# Leds_Indicadores.net
KiCad netlist of a schematic drawn in Altium Designer
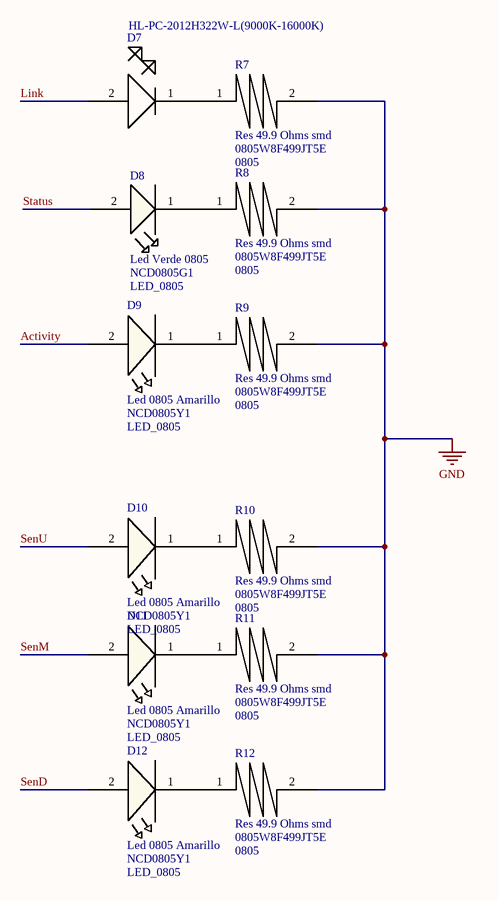
[diagram p0: Leds Indicadores.SchDoc]

(export (version "E")
  (design (tool "Eeschema 10.0.6"))
  (components
    (comp (ref "D7")
      (value "HL-PC-2012H322W-L(9000K-16000K)")
      (footprint "Led 0805 White")
      (libsource (lib "Integrated_Library") (part "LED White 0805"))
    )
    (comp (ref "D8")
      (value "Led Verde 0805")
      (footprint "Led 0805 Verde")
      (fields (field (name "MFR.PART #") "NCD0805G1") (field (name "PACKAGE") "LED_0805"))
      (libsource (lib "Integrated_Library") (part "Led 0805 Verde"))
    )
    (comp (ref "D9")
      (value "Led 0805 Amarillo")
      (footprint "Led 0805 Amarillo")
      (description "NCD0805Y1")
      (fields (field (name "MFR.PART #") "NCD0805Y1") (field (name "PACKAGE") "LED_0805"))
      (libsource (lib "Integrated_Library") (part "Led 0805 Amarillo"))
    )
    (comp (ref "D10")
      (value "Led 0805 Amarillo")
      (footprint "Led 0805 Amarillo")
      (description "NCD0805Y1")
      (fields (field (name "MFR.PART #") "NCD0805Y1") (field (name "PACKAGE") "LED_0805"))
      (libsource (lib "Integrated_Library") (part "Led 0805 Amarillo"))
    )
    (comp (ref "D11")
      (value "Led 0805 Amarillo")
      (footprint "Led 0805 Amarillo")
      (description "NCD0805Y1")
      (fields (field (name "MFR.PART #") "NCD0805Y1") (field (name "PACKAGE") "LED_0805"))
      (libsource (lib "Integrated_Library") (part "Led 0805 Amarillo"))
    )
    (comp (ref "D12")
      (value "Led 0805 Amarillo")
      (footprint "Led 0805 Amarillo")
      (description "NCD0805Y1")
      (fields (field (name "MFR.PART #") "NCD0805Y1") (field (name "PACKAGE") "LED_0805"))
      (libsource (lib "Integrated_Library") (part "Led 0805 Amarillo"))
    )
    (comp (ref "R7")
      (value "Res 49.9 Ohms smd")
      (footprint "RES 49.9 OHMS")
      (fields (field (name "MFR.PART #") "0805W8F499JT5E") (field (name "PACKAGE") "0805"))
      (libsource (lib "Integrated_Library") (part "Res 49.9 Ohms smd"))
    )
    (comp (ref "R8")
      (value "Res 49.9 Ohms smd")
      (footprint "RES 49.9 OHMS")
      (fields (field (name "MFR.PART #") "0805W8F499JT5E") (field (name "PACKAGE") "0805"))
      (libsource (lib "Integrated_Library") (part "Res 49.9 Ohms smd"))
    )
    (comp (ref "R9")
      (value "Res 49.9 Ohms smd")
      (footprint "RES 49.9 OHMS")
      (fields (field (name "MFR.PART #") "0805W8F499JT5E") (field (name "PACKAGE") "0805"))
      (libsource (lib "Integrated_Library") (part "Res 49.9 Ohms smd"))
    )
    (comp (ref "R10")
      (value "Res 49.9 Ohms smd")
      (footprint "RES 49.9 OHMS")
      (fields (field (name "MFR.PART #") "0805W8F499JT5E") (field (name "PACKAGE") "0805"))
      (libsource (lib "Integrated_Library") (part "Res 49.9 Ohms smd"))
    )
    (comp (ref "R11")
      (value "Res 49.9 Ohms smd")
      (footprint "RES 49.9 OHMS")
      (fields (field (name "MFR.PART #") "0805W8F499JT5E") (field (name "PACKAGE") "0805"))
      (libsource (lib "Integrated_Library") (part "Res 49.9 Ohms smd"))
    )
    (comp (ref "R12")
      (value "Res 49.9 Ohms smd")
      (footprint "RES 49.9 OHMS")
      (fields (field (name "MFR.PART #") "0805W8F499JT5E") (field (name "PACKAGE") "0805"))
      (libsource (lib "Integrated_Library") (part "Res 49.9 Ohms smd"))
    )
  )
  (nets
    (net (code "1") (name "/Activity") (class "Default")
      (node (ref "D9") (pin "2") (pinfunction "2_2") (pintype "passive"))
    )
    (net (code "2") (name "/Link") (class "Default")
      (node (ref "D7") (pin "2") (pinfunction "2_2") (pintype "passive"))
    )
    (net (code "3") (name "/SenD") (class "Default")
      (node (ref "D12") (pin "2") (pinfunction "2_2") (pintype "passive"))
    )
    (net (code "4") (name "/SenM") (class "Default")
      (node (ref "D11") (pin "2") (pinfunction "2_2") (pintype "passive"))
    )
    (net (code "5") (name "/SenU") (class "Default")
      (node (ref "D10") (pin "2") (pinfunction "2_2") (pintype "passive"))
    )
    (net (code "6") (name "/Status") (class "Default")
      (node (ref "D8") (pin "2") (pinfunction "2_2") (pintype "passive"))
    )
    (net (code "7") (name "GND") (class "Default")
      (node (ref "R10") (pin "2") (pinfunction "2_2") (pintype "passive"))
      (node (ref "R11") (pin "2") (pinfunction "2_2") (pintype "passive"))
      (node (ref "R12") (pin "2") (pinfunction "2_2") (pintype "passive"))
      (node (ref "R7") (pin "2") (pinfunction "2_2") (pintype "passive"))
      (node (ref "R8") (pin "2") (pinfunction "2_2") (pintype "passive"))
      (node (ref "R9") (pin "2") (pinfunction "2_2") (pintype "passive"))
    )
    (net (code "8") (name "Net-(D7-Pad1)") (class "Default")
      (node (ref "D7") (pin "1") (pinfunction "1_1") (pintype "passive"))
      (node (ref "R7") (pin "1") (pinfunction "1_1") (pintype "passive"))
    )
    (net (code "9") (name "Net-(D8-Pad1)") (class "Default")
      (node (ref "D8") (pin "1") (pintype "passive"))
      (node (ref "R8") (pin "1") (pinfunction "1_1") (pintype "passive"))
    )
    (net (code "10") (name "Net-(D9-Pad1)") (class "Default")
      (node (ref "D9") (pin "1") (pinfunction "1_1") (pintype "passive"))
      (node (ref "R9") (pin "1") (pinfunction "1_1") (pintype "passive"))
    )
    (net (code "11") (name "Net-(D10-Pad1)") (class "Default")
      (node (ref "D10") (pin "1") (pinfunction "1_1") (pintype "passive"))
      (node (ref "R10") (pin "1") (pinfunction "1_1") (pintype "passive"))
    )
    (net (code "12") (name "Net-(D11-Pad1)") (class "Default")
      (node (ref "D11") (pin "1") (pinfunction "1_1") (pintype "passive"))
      (node (ref "R11") (pin "1") (pinfunction "1_1") (pintype "passive"))
    )
    (net (code "13") (name "Net-(D12-Pad1)") (class "Default")
      (node (ref "D12") (pin "1") (pinfunction "1_1") (pintype "passive"))
      (node (ref "R12") (pin "1") (pinfunction "1_1") (pintype "passive"))
    )
  )
)
